# Projeto_Final.net
KiCad netlist of a schematic drawn in EAGLE
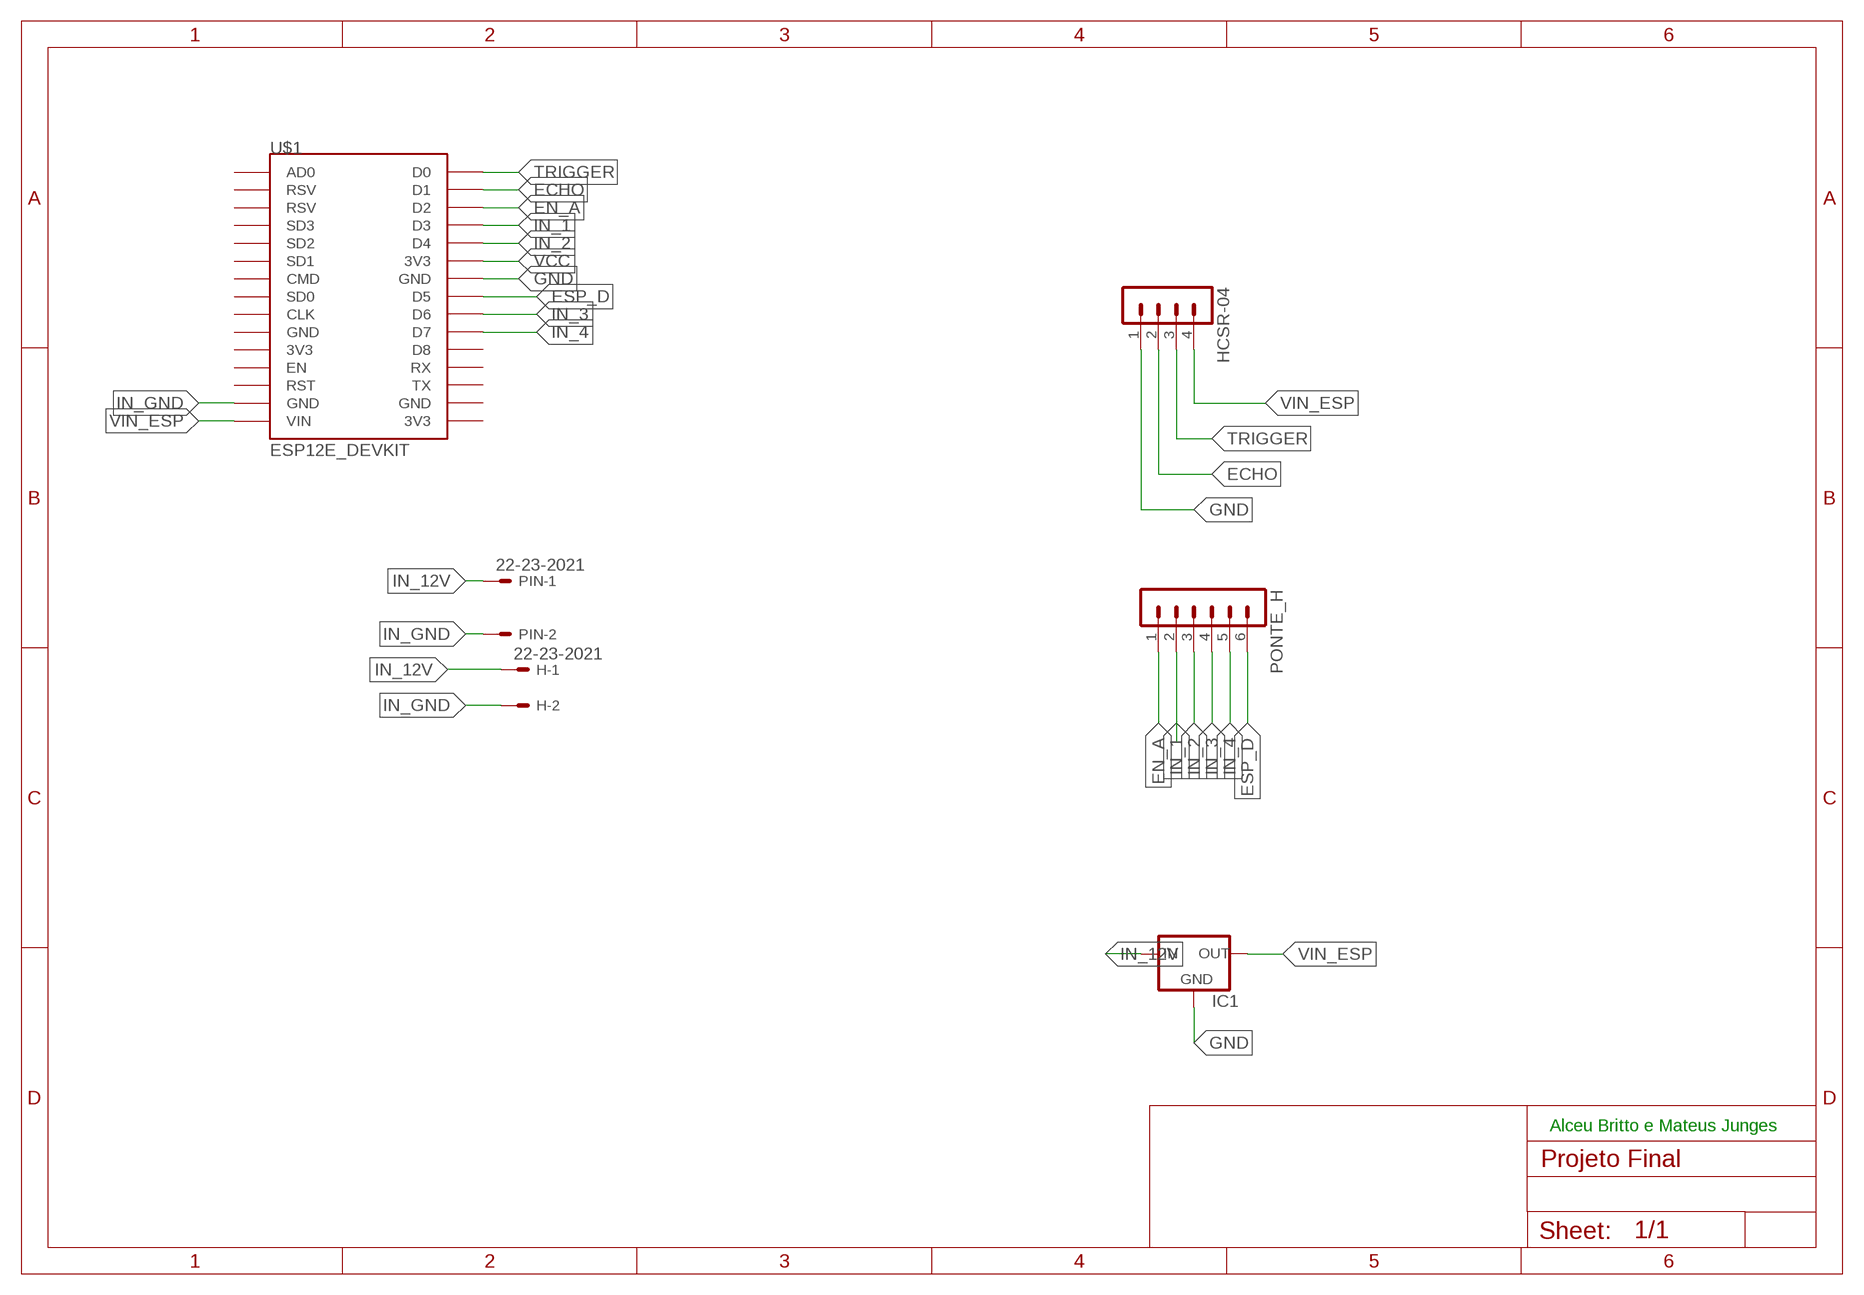
[diagram p0: schematic, sheet 1]

(export (version "E")
  (design (tool "Eeschema 10.0.6"))
  (components
    (comp (ref "H")
      (value "22-23-2021")
      (footprint "eagle-import:22-23-2021")
      (fields (field (name "MF") "MOLEX"))
      (libsource (lib "eagle-import") (part "22-23-2021"))
    )
    (comp (ref "HCSR-04")
      (value "MA04-1")
      (footprint "eagle-import:MA04-1")
      (libsource (lib "eagle-import") (part "MA04-1"))
    )
    (comp (ref "IC1")
      (value "78XXL")
      (footprint "eagle-import:78XXL")
      (libsource (lib "eagle-import") (part "78XXL"))
    )
    (comp (ref "PIN")
      (value "22-23-2021")
      (footprint "eagle-import:22-23-2021")
      (fields (field (name "MF") "MOLEX"))
      (libsource (lib "eagle-import") (part "22-23-2021"))
    )
    (comp (ref "PONTE_H")
      (value "MA06-1")
      (footprint "eagle-import:MA06-1")
      (libsource (lib "eagle-import") (part "MA06-1"))
    )
    (comp (ref "U$1")
      (value "ESP12E_DEVKIT")
      (footprint "eagle-import:ESP12E_DEVKIT")
      (libsource (lib "eagle-import") (part "ESP12E_DEVKIT"))
    )
  )
  (nets
    (net (code "1") (name "ECHO") (class "Default")
      (node (ref "HCSR-04") (pin "2") (pinfunction "2_2") (pintype "passive"))
      (node (ref "U$1") (pin "D1") (pinfunction "D1_D1") (pintype "bidirectional"))
    )
    (net (code "2") (name "EN_A") (class "Default")
      (node (ref "PONTE_H") (pin "1") (pinfunction "1_1") (pintype "passive"))
      (node (ref "U$1") (pin "D2") (pinfunction "D2_D2") (pintype "bidirectional"))
    )
    (net (code "3") (name "ESP_D") (class "Default")
      (node (ref "PONTE_H") (pin "6") (pinfunction "6_6") (pintype "passive"))
      (node (ref "U$1") (pin "D5") (pinfunction "D5_D5") (pintype "bidirectional"))
    )
    (net (code "4") (name "GND") (class "Default")
      (node (ref "HCSR-04") (pin "1") (pinfunction "1_1") (pintype "passive"))
      (node (ref "IC1") (pin "GND") (pinfunction "GND_GND") (pintype "input"))
      (node (ref "U$1") (pin "GND@2") (pinfunction "GND_GND@2") (pintype "bidirectional"))
    )
    (net (code "5") (name "IN_1") (class "Default")
      (node (ref "PONTE_H") (pin "2") (pinfunction "2_2") (pintype "passive"))
      (node (ref "U$1") (pin "D3") (pinfunction "D3_D3") (pintype "bidirectional"))
    )
    (net (code "6") (name "IN_2") (class "Default")
      (node (ref "PONTE_H") (pin "3") (pinfunction "3_3") (pintype "passive"))
      (node (ref "U$1") (pin "D4") (pinfunction "D4_D4") (pintype "bidirectional"))
    )
    (net (code "7") (name "IN_3") (class "Default")
      (node (ref "PONTE_H") (pin "4") (pinfunction "4_4") (pintype "passive"))
      (node (ref "U$1") (pin "D6") (pinfunction "D6_D6") (pintype "bidirectional"))
    )
    (net (code "8") (name "IN_4") (class "Default")
      (node (ref "PONTE_H") (pin "5") (pinfunction "5_5") (pintype "passive"))
      (node (ref "U$1") (pin "D7") (pinfunction "D7_D7") (pintype "bidirectional"))
    )
    (net (code "9") (name "IN_12V") (class "Default")
      (node (ref "H") (pin "1") (pinfunction "S_1") (pintype "passive"))
      (node (ref "IC1") (pin "IN") (pinfunction "IN_IN") (pintype "input"))
      (node (ref "PIN") (pin "1") (pinfunction "S_1") (pintype "passive"))
    )
    (net (code "10") (name "IN_GND") (class "Default")
      (node (ref "H") (pin "2") (pinfunction "S_2") (pintype "passive"))
      (node (ref "PIN") (pin "2") (pinfunction "S_2") (pintype "passive"))
      (node (ref "U$1") (pin "GND@1") (pinfunction "GND_GND@1") (pintype "bidirectional"))
    )
    (net (code "11") (name "TRIGGER") (class "Default")
      (node (ref "HCSR-04") (pin "3") (pinfunction "3_3") (pintype "passive"))
      (node (ref "U$1") (pin "D0") (pinfunction "D0_D0") (pintype "bidirectional"))
    )
    (net (code "12") (name "VCC") (class "Default")
      (node (ref "U$1") (pin "3V3@1") (pinfunction "3V3_3V3@1") (pintype "bidirectional"))
    )
    (net (code "13") (name "VIN_ESP") (class "Default")
      (node (ref "HCSR-04") (pin "4") (pinfunction "4_4") (pintype "passive"))
      (node (ref "IC1") (pin "OUT") (pinfunction "OUT_OUT") (pintype "passive"))
      (node (ref "U$1") (pin "VIN") (pinfunction "VIN_VIN") (pintype "bidirectional"))
    )
    (net (code "14") (name "unconnected-(U$1-3V3-Pad3V3@0)") (class "Default")
      (node (ref "U$1") (pin "3V3@0") (pinfunction "3V3_3V3@0") (pintype "bidirectional"))
    )
    (net (code "15") (name "unconnected-(U$1-3V3-Pad3V3@2)") (class "Default")
      (node (ref "U$1") (pin "3V3@2") (pinfunction "3V3_3V3@2") (pintype "bidirectional"))
    )
    (net (code "16") (name "unconnected-(U$1-GND-PadGND@0)") (class "Default")
      (node (ref "U$1") (pin "GND@0") (pinfunction "GND_GND@0") (pintype "bidirectional"))
    )
    (net (code "17") (name "unconnected-(U$1-GND-PadGND@3)") (class "Default")
      (node (ref "U$1") (pin "GND@3") (pinfunction "GND_GND@3") (pintype "bidirectional"))
    )
    (net (code "18") (name "unconnected-(U$1-PadAD0)") (class "Default")
      (node (ref "U$1") (pin "AD0") (pinfunction "AD0_AD0") (pintype "bidirectional"))
    )
    (net (code "19") (name "unconnected-(U$1-PadCLK)") (class "Default")
      (node (ref "U$1") (pin "CLK") (pinfunction "CLK_CLK") (pintype "bidirectional"))
    )
    (net (code "20") (name "unconnected-(U$1-PadCMD)") (class "Default")
      (node (ref "U$1") (pin "CMD") (pinfunction "CMD_CMD") (pintype "bidirectional"))
    )
    (net (code "21") (name "unconnected-(U$1-PadD8)") (class "Default")
      (node (ref "U$1") (pin "D8") (pinfunction "D8_D8") (pintype "bidirectional"))
    )
    (net (code "22") (name "unconnected-(U$1-PadEN)") (class "Default")
      (node (ref "U$1") (pin "EN") (pinfunction "EN_EN") (pintype "bidirectional"))
    )
    (net (code "23") (name "unconnected-(U$1-PadRST)") (class "Default")
      (node (ref "U$1") (pin "RST") (pinfunction "RST_RST") (pintype "bidirectional"))
    )
    (net (code "24") (name "unconnected-(U$1-PadRX)") (class "Default")
      (node (ref "U$1") (pin "RX") (pinfunction "RX_RX") (pintype "bidirectional"))
    )
    (net (code "25") (name "unconnected-(U$1-PadSD0)") (class "Default")
      (node (ref "U$1") (pin "SD0") (pinfunction "SD0_SD0") (pintype "bidirectional"))
    )
    (net (code "26") (name "unconnected-(U$1-PadSD1)") (class "Default")
      (node (ref "U$1") (pin "SD1") (pinfunction "SD1_SD1") (pintype "bidirectional"))
    )
    (net (code "27") (name "unconnected-(U$1-PadSD2)") (class "Default")
      (node (ref "U$1") (pin "SD2") (pinfunction "SD2_SD2") (pintype "bidirectional"))
    )
    (net (code "28") (name "unconnected-(U$1-PadSD3)") (class "Default")
      (node (ref "U$1") (pin "SD3") (pinfunction "SD3_SD3") (pintype "bidirectional"))
    )
    (net (code "29") (name "unconnected-(U$1-PadTX)") (class "Default")
      (node (ref "U$1") (pin "TX") (pinfunction "TX_TX") (pintype "bidirectional"))
    )
    (net (code "30") (name "unconnected-(U$1-RSV-PadRSV@0)") (class "Default")
      (node (ref "U$1") (pin "RSV@0") (pinfunction "RSV_RSV@0") (pintype "bidirectional"))
    )
    (net (code "31") (name "unconnected-(U$1-RSV-PadRSV@1)") (class "Default")
      (node (ref "U$1") (pin "RSV@1") (pinfunction "RSV_RSV@1") (pintype "bidirectional"))
    )
  )
)
